# NTC.net
KiCad netlist of a schematic drawn in Altium Designer
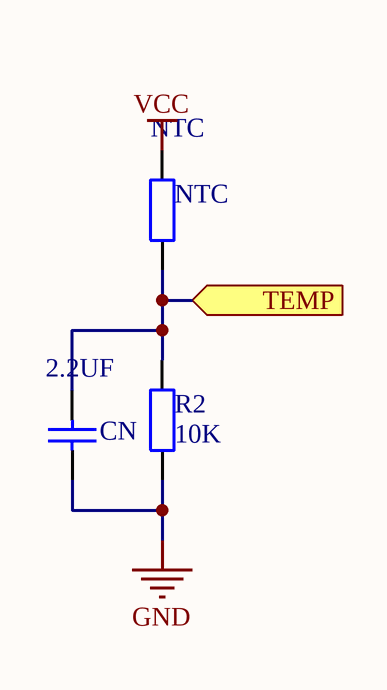
[diagram p0: NTC.SchDoc]

(export (version "E")
  (design (tool "Eeschema 10.0.6"))
  (components
    (comp (ref "CN")
      (value "2.2UF")
      (footprint "C-0603")
      (description "Capacitor")
      (fields (field (name "PUBLISHER") "Altium Limited"))
      (libsource (lib "TAOXUN") (part "CAP"))
    )
    (comp (ref "NTC")
      (value "NTC")
      (footprint "0603-2")
      (description "贴片电阻")
      (fields (field (name "PUBLISHER") "Altium Limited"))
      (libsource (lib "TAOXUN") (part "Res1"))
    )
    (comp (ref "R2")
      (value "10K")
      (footprint "0402")
      (description "贴片电阻")
      (fields (field (name "PUBLISHER") "Altium Limited"))
      (libsource (lib "TAOXUN") (part "Res1"))
    )
  )
  (nets
    (net (code "1") (name "/TEMP") (class "Default")
      (node (ref "CN") (pin "2") (pinfunction "2_2") (pintype "passive"))
      (node (ref "NTC") (pin "1") (pinfunction "1_1") (pintype "passive"))
      (node (ref "R2") (pin "2") (pinfunction "2_2") (pintype "passive"))
    )
    (net (code "2") (name "GND") (class "Default")
      (node (ref "CN") (pin "1") (pinfunction "1_1") (pintype "passive"))
      (node (ref "R2") (pin "1") (pinfunction "1_1") (pintype "passive"))
    )
    (net (code "3") (name "VCC") (class "Default")
      (node (ref "NTC") (pin "2") (pinfunction "2_2") (pintype "passive"))
    )
  )
)
